# Agrobot_3_0.net
KiCad netlist of a schematic drawn in Altium Designer
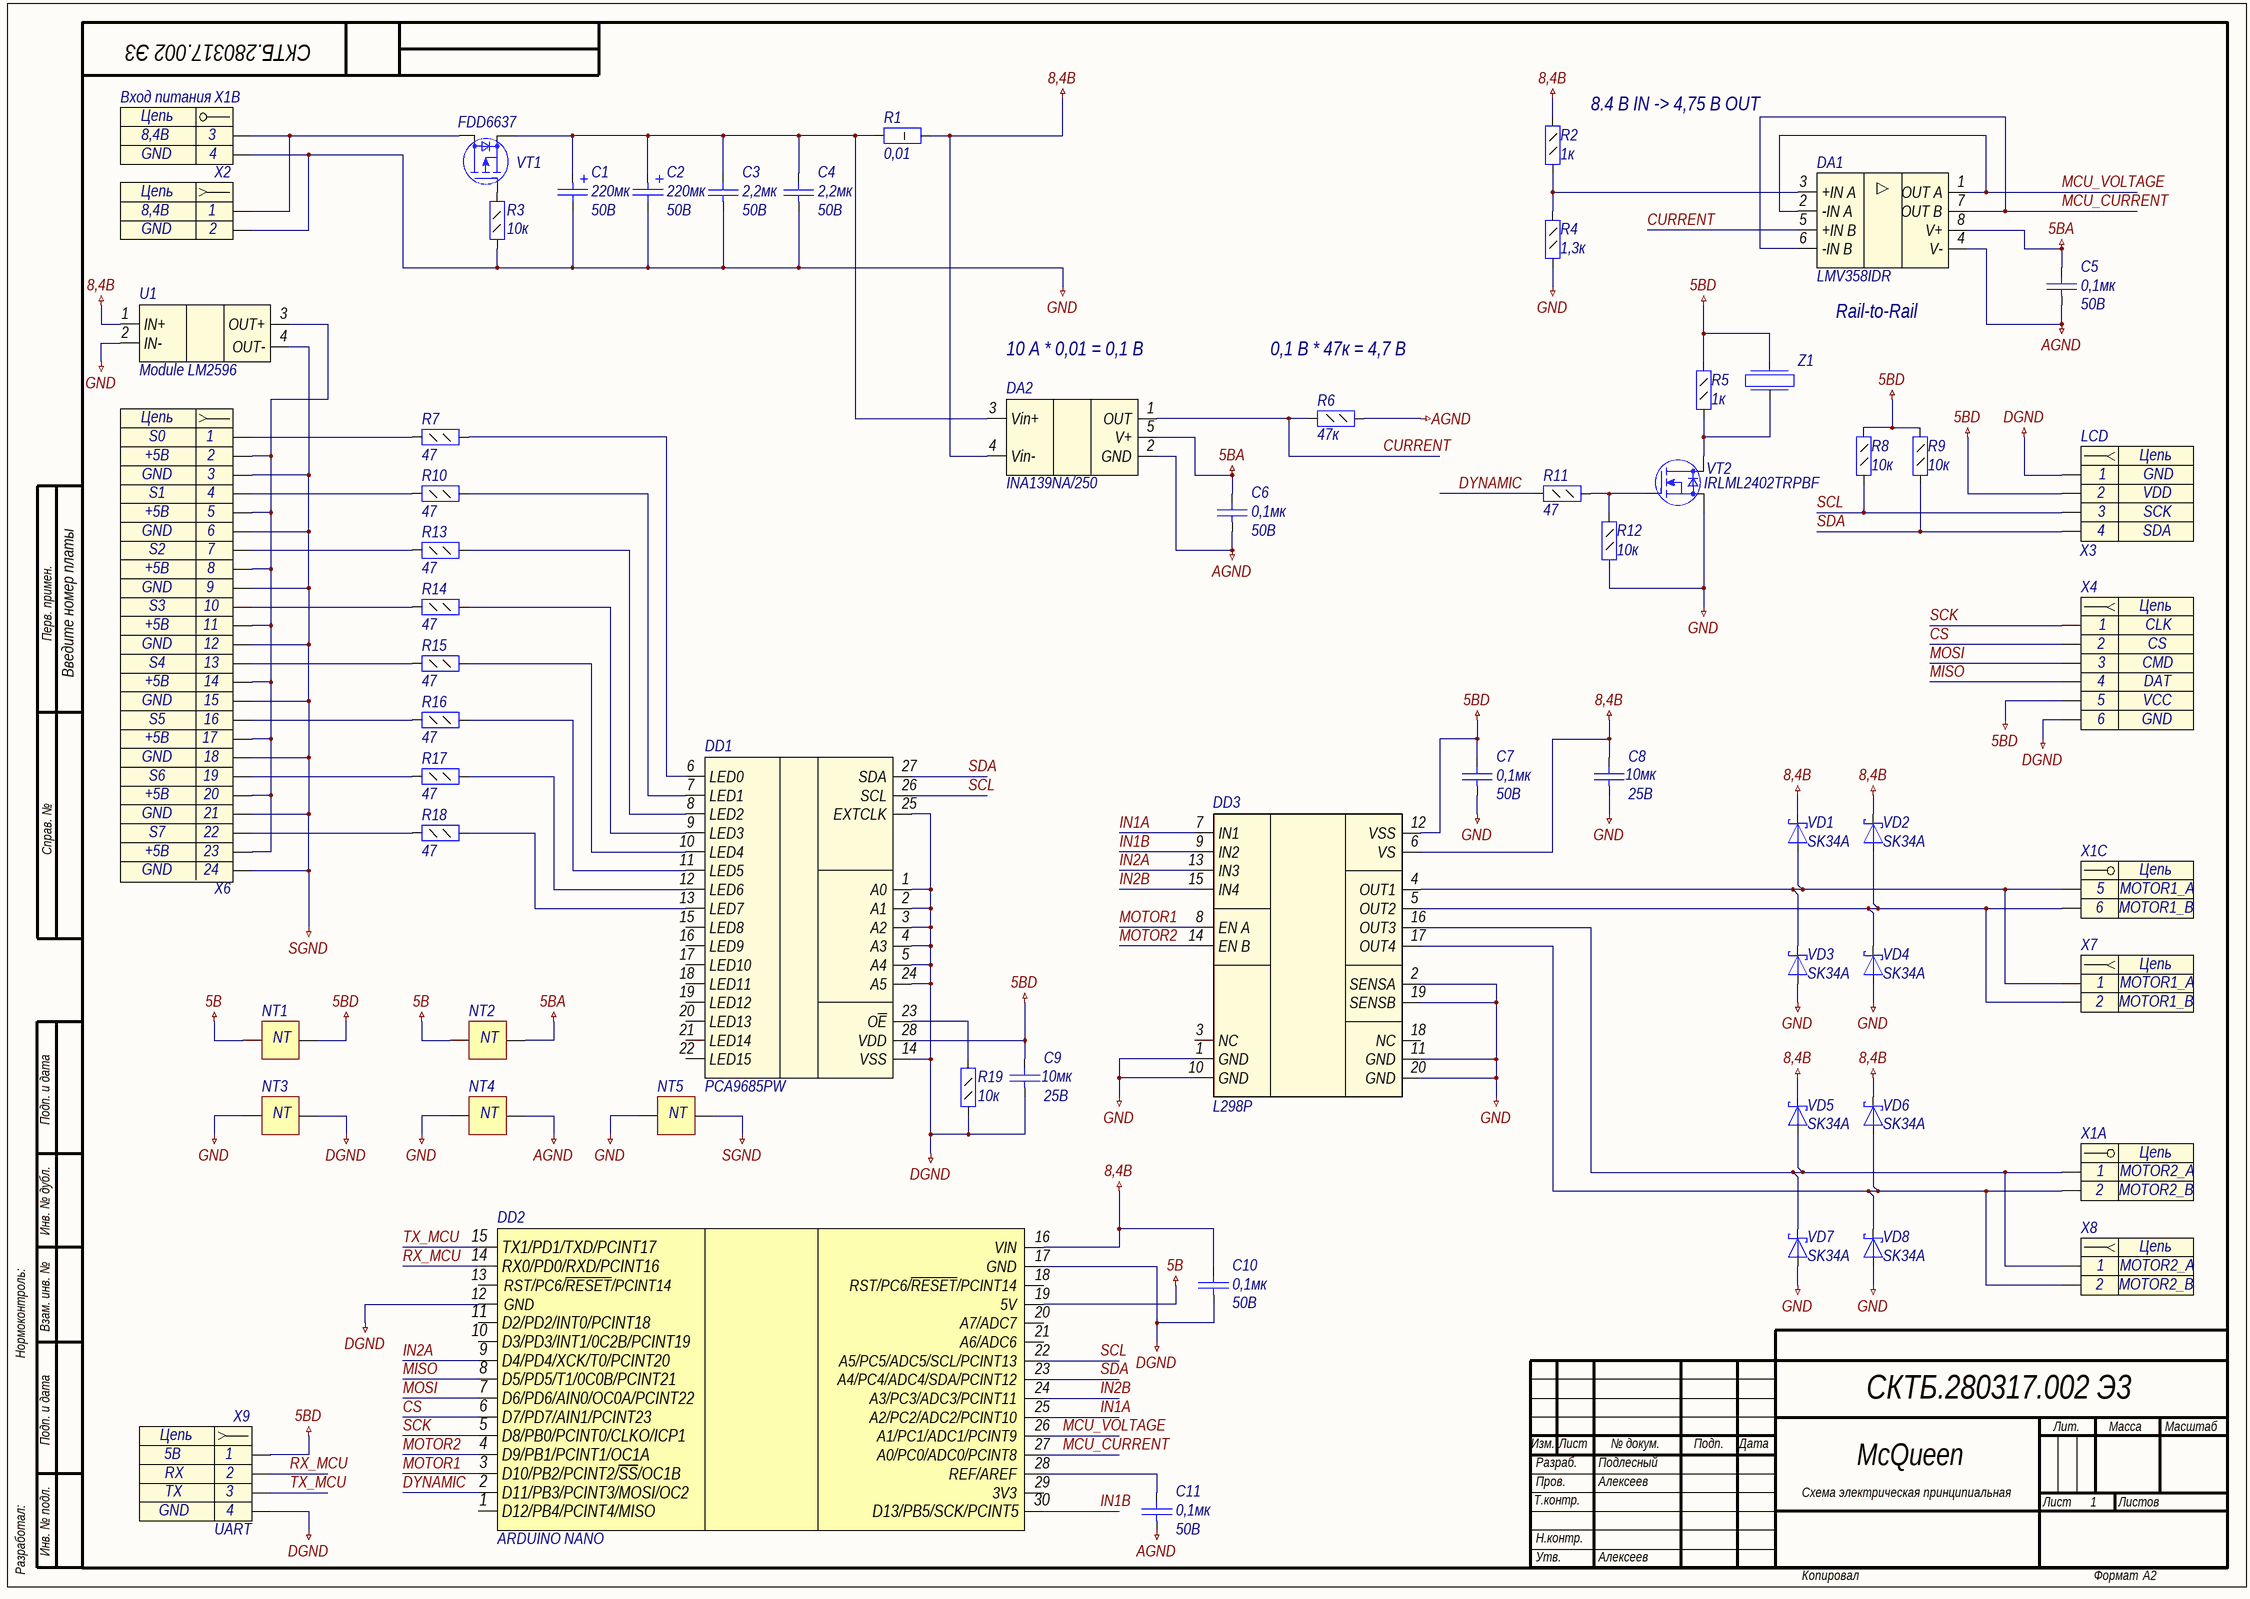
[diagram p0: Agrobot_3.0.SchDoc]

(export (version "E")
  (design (tool "Eeschema 10.0.6"))
  (components
    (comp (ref "C1")
      (value "220мк")
      (footprint "Cap_SMD_radial_polar(10x10.5)")
      (description "Конденсатор полярный")
      (fields
        (field (name "VOLTAGE") "50В")
        (field (name "PART NUMBER") "ECAP SMD")
        (field (name "Comment") "Capacitor_pol")
      )
      (libsource (lib "MOP44") (part "Capacitor_pol"))
    )
    (comp (ref "C2")
      (value "220мк")
      (footprint "Cap_SMD_radial_polar(10x10.5)")
      (description "Конденсатор полярный")
      (fields
        (field (name "VOLTAGE") "50В")
        (field (name "PART NUMBER") "ECAP SMD")
        (field (name "Comment") "Capacitor_pol")
      )
      (libsource (lib "MOP44") (part "Capacitor_pol"))
    )
    (comp (ref "C3")
      (value "2,2мк")
      (footprint "C1206")
      (description "Конденсатор")
      (fields
        (field (name "VOLTAGE") "50В")
        (field (name "PART NUMBER") "GRM31CR71H225KA88**L")
        (field (name "Comment") "Capacitor")
      )
      (libsource (lib "MOP44") (part "Capacitor"))
    )
    (comp (ref "C4")
      (value "2,2мк")
      (footprint "C1206")
      (description "Конденсатор")
      (fields
        (field (name "VOLTAGE") "50В")
        (field (name "PART NUMBER") "GRM31CR71H225KA88**L")
        (field (name "Comment") "Capacitor")
      )
      (libsource (lib "MOP44") (part "Capacitor"))
    )
    (comp (ref "C5")
      (value "0,1мк")
      (footprint "C0805")
      (description "Конденсатор")
      (fields
        (field (name "VOLTAGE") "50B")
        (field (name "PART NUMBER") "GRM21BR71E225K")
        (field (name "Comment") "Capacitor")
      )
      (libsource (lib "MOP44") (part "Capacitor"))
    )
    (comp (ref "C6")
      (value "0,1мк")
      (footprint "C0805")
      (description "Конденсатор")
      (fields
        (field (name "VOLTAGE") "50B")
        (field (name "PART NUMBER") "GRM21BR71E225K")
        (field (name "Comment") "Capacitor")
      )
      (libsource (lib "MOP44") (part "Capacitor"))
    )
    (comp (ref "C7")
      (value "0,1мк")
      (footprint "C0805")
      (description "Конденсатор")
      (fields
        (field (name "VOLTAGE") "50B")
        (field (name "PART NUMBER") "GRM21BR71E225K")
        (field (name "Comment") "Capacitor")
      )
      (libsource (lib "MOP44") (part "Capacitor"))
    )
    (comp (ref "C8")
      (value "10мк")
      (footprint "C1210")
      (description "Конденсатор")
      (fields
        (field (name "VOLTAGE") "25В")
        (field (name "PART NUMBER") "GRM32ER61A106K")
        (field (name "Comment") "Capacitor")
      )
      (libsource (lib "MOP44") (part "Capacitor"))
    )
    (comp (ref "C9")
      (value "10мк")
      (footprint "C1210")
      (description "Конденсатор")
      (fields
        (field (name "VOLTAGE") "25В")
        (field (name "PART NUMBER") "GRM32ER61A106K")
        (field (name "Comment") "Capacitor")
      )
      (libsource (lib "MOP44") (part "Capacitor"))
    )
    (comp (ref "C10")
      (value "0,1мк")
      (footprint "C0805")
      (description "Конденсатор")
      (fields
        (field (name "VOLTAGE") "50B")
        (field (name "PART NUMBER") "GRM21BR71E225K")
        (field (name "Comment") "Capacitor")
      )
      (libsource (lib "MOP44") (part "Capacitor"))
    )
    (comp (ref "C11")
      (value "0,1мк")
      (footprint "C0805")
      (description "Конденсатор")
      (fields
        (field (name "VOLTAGE") "50B")
        (field (name "PART NUMBER") "GRM21BR71E225K")
        (field (name "Comment") "Capacitor")
      )
      (libsource (lib "MOP44") (part "Capacitor"))
    )
    (comp (ref "DA1")
      (value "LMV358IDR")
      (footprint "SO8")
      (description "LOW-VOLTAGE RAIL-TO-RAIL OUTPUT OPERATIONAL AMPLIFIERS")
      (libsource (lib "MOP44") (part "LMV358IDR"))
    )
    (comp (ref "DA2")
      (value "INA139NA/250")
      (footprint "SOT23-5")
      (description "Измерительный датчик тока")
      (libsource (lib "MOP44") (part "INA139NA/250"))
    )
    (comp (ref "DD1")
      (value "PCA9685PW")
      (footprint "TSSOP28")
      (description "Драйвер светодиода, 16 выходов")
      (libsource (lib "MOP44") (part "PCA9685PW"))
    )
    (comp (ref "DD2")
      (value "ARDUINO NANO")
      (footprint "ARDUINO NANO")
      (description "Отладочная плата ATmega328")
      (libsource (lib "MOP44") (part "ARDUINO NANO"))
    )
    (comp (ref "DD3")
      (value "L298P")
      (footprint "POWERSO20")
      (description "FULL BRIDGE DC MOTOR DRIVER")
      (libsource (lib "MOP44") (part "L298P"))
    )
    (comp (ref "NT1")
      (value "Pofigistor")
      (footprint "Pofigistor0603")
      (libsource (lib "MOP44") (part "Pofigistor"))
    )
    (comp (ref "NT2")
      (value "Pofigistor")
      (footprint "Pofigistor0603")
      (libsource (lib "MOP44") (part "Pofigistor"))
    )
    (comp (ref "NT3")
      (value "Pofigistor")
      (footprint "Pofigistor0603")
      (libsource (lib "MOP44") (part "Pofigistor"))
    )
    (comp (ref "NT4")
      (value "Pofigistor")
      (footprint "Pofigistor0603")
      (libsource (lib "MOP44") (part "Pofigistor"))
    )
    (comp (ref "NT5")
      (value "Pofigistor")
      (footprint "Pofigistor0603")
      (libsource (lib "MOP44") (part "Pofigistor"))
    )
    (comp (ref "R1")
      (value "0,01")
      (footprint "R2512")
      (description "Резистор")
      (fields (field (name "POWER") "1Вт") (field (name "Comment") "Resistor_1Вт"))
      (libsource (lib "MOP44") (part "Resistor_1Вт"))
    )
    (comp (ref "R2")
      (value "1к")
      (footprint "R0805")
      (description "Резистор")
      (fields (field (name "POWER") "0,125Вт") (field (name "Comment") "Resistor_0,125Вт"))
      (libsource (lib "") (part "Resistor_0,125Вт_1"))
    )
    (comp (ref "R3")
      (value "10к")
      (footprint "R0805")
      (description "Резистор")
      (fields (field (name "PART NUMBER") "RC0805FR-0710KL") (field (name "POWER") "0,125Вт"))
      (libsource (lib "") (part "Resistor_0,125Вт_2"))
    )
    (comp (ref "R4")
      (value "1,3к")
      (footprint "R0805")
      (description "Резистор")
      (fields (field (name "POWER") "0,125Вт") (field (name "Comment") "Resistor_0,125Вт"))
      (libsource (lib "") (part "Resistor_0,125Вт_1"))
    )
    (comp (ref "R5")
      (value "1к")
      (footprint "R0805")
      (description "Резистор")
      (fields (field (name "POWER") "0,125Вт") (field (name "Comment") "Resistor_0,125Вт"))
      (libsource (lib "") (part "Resistor_0,125Вт_1"))
    )
    (comp (ref "R6")
      (value "47к")
      (footprint "R0805")
      (description "Резистор")
      (fields (field (name "POWER") "0,125Вт") (field (name "Comment") "Resistor_0,125Вт"))
      (libsource (lib "") (part "Resistor_0,125Вт_3"))
    )
    (comp (ref "R7")
      (value "47")
      (footprint "R0805")
      (description "Резистор")
      (fields (field (name "PART NUMBER") "RC0805FR-0747RL") (field (name "POWER") "0,125Вт"))
      (libsource (lib "MOP44") (part "Resistor_0,125Вт"))
    )
    (comp (ref "R8")
      (value "10к")
      (footprint "R0805")
      (description "Резистор")
      (fields (field (name "POWER") "0,125Вт") (field (name "Comment") "Resistor_0,125Вт"))
      (libsource (lib "") (part "Resistor_0,125Вт_1"))
    )
    (comp (ref "R9")
      (value "10к")
      (footprint "R0805")
      (description "Резистор")
      (fields (field (name "POWER") "0,125Вт") (field (name "Comment") "Resistor_0,125Вт"))
      (libsource (lib "") (part "Resistor_0,125Вт_1"))
    )
    (comp (ref "R10")
      (value "47")
      (footprint "R0805")
      (description "Резистор")
      (fields (field (name "PART NUMBER") "RC0805FR-0747RL") (field (name "POWER") "0,125Вт"))
      (libsource (lib "MOP44") (part "Resistor_0,125Вт"))
    )
    (comp (ref "R11")
      (value "47")
      (footprint "R0805")
      (description "Резистор")
      (fields (field (name "POWER") "0,125Вт") (field (name "Comment") "Resistor_0,125Вт"))
      (libsource (lib "") (part "Resistor_0,125Вт_3"))
    )
    (comp (ref "R12")
      (value "10к")
      (footprint "R0805")
      (description "Резистор")
      (fields (field (name "POWER") "0,125Вт") (field (name "Comment") "Resistor_0,125Вт"))
      (libsource (lib "") (part "Resistor_0,125Вт_1"))
    )
    (comp (ref "R13")
      (value "47")
      (footprint "R0805")
      (description "Резистор")
      (fields (field (name "PART NUMBER") "RC0805FR-0747RL") (field (name "POWER") "0,125Вт"))
      (libsource (lib "MOP44") (part "Resistor_0,125Вт"))
    )
    (comp (ref "R14")
      (value "47")
      (footprint "R0805")
      (description "Резистор")
      (fields (field (name "PART NUMBER") "RC0805FR-0747RL") (field (name "POWER") "0,125Вт"))
      (libsource (lib "MOP44") (part "Resistor_0,125Вт"))
    )
    (comp (ref "R15")
      (value "47")
      (footprint "R0805")
      (description "Резистор")
      (fields (field (name "PART NUMBER") "RC0805FR-0747RL") (field (name "POWER") "0,125Вт"))
      (libsource (lib "MOP44") (part "Resistor_0,125Вт"))
    )
    (comp (ref "R16")
      (value "47")
      (footprint "R0805")
      (description "Резистор")
      (fields (field (name "PART NUMBER") "RC0805FR-0747RL") (field (name "POWER") "0,125Вт"))
      (libsource (lib "MOP44") (part "Resistor_0,125Вт"))
    )
    (comp (ref "R17")
      (value "47")
      (footprint "R0805")
      (description "Резистор")
      (fields (field (name "PART NUMBER") "RC0805FR-0747RL") (field (name "POWER") "0,125Вт"))
      (libsource (lib "MOP44") (part "Resistor_0,125Вт"))
    )
    (comp (ref "R18")
      (value "47")
      (footprint "R0805")
      (description "Резистор")
      (fields (field (name "PART NUMBER") "RC0805FR-0747RL") (field (name "POWER") "0,125Вт"))
      (libsource (lib "MOP44") (part "Resistor_0,125Вт"))
    )
    (comp (ref "R19")
      (value "10к")
      (footprint "R0805")
      (description "Резистор")
      (fields (field (name "POWER") "0,125Вт") (field (name "Comment") "Resistor_0,125Вт"))
      (libsource (lib "") (part "Resistor_0,125Вт_2"))
    )
    (comp (ref "U1")
      (value "Module LM2596")
      (footprint "module LM2596")
      (description "Low-Dropout Regulator for 5-V to 3.3-V Conversion")
      (libsource (lib "MOP44") (part "Module LM2596"))
    )
    (comp (ref "VD1")
      (value "DiodeSchottky")
      (footprint "SMA")
      (description "Диод Шоттки")
      (fields (field (name "PART NUMBER") "SK34A"))
      (libsource (lib "MOP44") (part "DiodeSchottky"))
    )
    (comp (ref "VD2")
      (value "DiodeSchottky")
      (footprint "SMA")
      (description "Диод Шоттки")
      (fields (field (name "PART NUMBER") "SK34A"))
      (libsource (lib "MOP44") (part "DiodeSchottky"))
    )
    (comp (ref "VD3")
      (value "DiodeSchottky")
      (footprint "SMA")
      (description "Диод Шоттки")
      (fields (field (name "PART NUMBER") "SK34A"))
      (libsource (lib "MOP44") (part "DiodeSchottky"))
    )
    (comp (ref "VD4")
      (value "DiodeSchottky")
      (footprint "SMA")
      (description "Диод Шоттки")
      (fields (field (name "PART NUMBER") "SK34A"))
      (libsource (lib "MOP44") (part "DiodeSchottky"))
    )
    (comp (ref "VD5")
      (value "DiodeSchottky")
      (footprint "SMA")
      (description "Диод Шоттки")
      (fields (field (name "PART NUMBER") "SK34A"))
      (libsource (lib "MOP44") (part "DiodeSchottky"))
    )
    (comp (ref "VD6")
      (value "DiodeSchottky")
      (footprint "SMA")
      (description "Диод Шоттки")
      (fields (field (name "PART NUMBER") "SK34A"))
      (libsource (lib "MOP44") (part "DiodeSchottky"))
    )
    (comp (ref "VD7")
      (value "DiodeSchottky")
      (footprint "SMA")
      (description "Диод Шоттки")
      (fields (field (name "PART NUMBER") "SK34A"))
      (libsource (lib "MOP44") (part "DiodeSchottky"))
    )
    (comp (ref "VD8")
      (value "DiodeSchottky")
      (footprint "SMA")
      (description "Диод Шоттки")
      (fields (field (name "PART NUMBER") "SK34A"))
      (libsource (lib "MOP44") (part "DiodeSchottky"))
    )
    (comp (ref "VT1")
      (value "P-MOSFET")
      (footprint "DPAK")
      (description "N-MOSFET")
      (fields (field (name "PART NUMBER") "FDD6637") (field (name "MANUFACTURER") "Fairchild Semiconductor"))
      (libsource (lib "MOP44") (part "P-MOSFET"))
    )
    (comp (ref "VT2")
      (value "N-MOSFET")
      (footprint "SOT23-3")
      (fields (field (name "PART NUMBER") "IRLML2402TRPBF"))
      (libsource (lib "MOP44") (part "N-MOSFET"))
    )
    (comp (ref "X1")
      (value "Вход питания")
      (footprint "TERMINAL-6WAY-5MM")
      (description "POWER")
      (libsource (lib "MOP44") (part "Header_6_motor"))
    )
    (comp (ref "X2")
      (value "Header_2_sct")
      (footprint "2HOLE_2.5")
      (description "Разъем - 2 конт. розетка")
      (libsource (lib "") (part "Header_2_sct_1"))
    )
    (comp (ref "X3")
      (value "LCD")
      (footprint "PLS-4HOLES")
      (description "Разъем - 4 конт. розетка")
      (libsource (lib "") (part "Header_4_sct_1"))
    )
    (comp (ref "X4")
      (value "Header_6_sct")
      (footprint "PSP_ANTENNA")
      (description "Разъем - 6 конт. розетка")
      (libsource (lib "MOP44") (part "Header_6_sct"))
    )
    (comp (ref "X6")
      (value "Header_24_sct")
      (footprint "PLS-24-3")
      (description "Разъем - 5 конт. розетка")
      (libsource (lib "MOP44") (part "Header_24_sct"))
    )
    (comp (ref "X7")
      (value "Header_2_sct")
      (footprint "2HOLE_2.5")
      (description "Разъем - 2 конт. розетка")
      (libsource (lib "MOP44") (part "Header_2_sct"))
    )
    (comp (ref "X8")
      (value "Header_2_sct")
      (footprint "2HOLE_2.5")
      (description "Разъем - 2 конт. розетка")
      (libsource (lib "MOP44") (part "Header_2_sct"))
    )
    (comp (ref "X9")
      (value "UART")
      (footprint "PLS-4HOLES")
      (description "Разъем - 4 конт. розетка")
      (libsource (lib "MOP44") (part "Header_4_sct"))
    )
    (comp (ref "Z1")
      (value "~")
      (footprint "Buzzer_9mm")
      (description "Пьезоизлучатель звуковой без генератора")
      (fields (field (name "PART NUMBER") "HC0905F"))
      (libsource (lib "MOP44") (part "Buzzer"))
    )
  )
  (nets
    (net (code "1") (name "/CS") (class "Default")
      (node (ref "DD2") (pin "6") (pinfunction "D7/PD7/AIN1/PCINT23_6") (pintype "passive"))
      (node (ref "X4") (pin "2") (pinfunction "2_2") (pintype "passive"))
    )
    (net (code "2") (name "/CURRENT") (class "Default")
      (node (ref "DA1") (pin "5") (pinfunction "+IN_B_5") (pintype "passive"))
      (node (ref "DA2") (pin "1") (pinfunction "OUT_1") (pintype "power_in"))
      (node (ref "R6") (pin "2") (pinfunction "2_2") (pintype "passive"))
    )
    (net (code "3") (name "/DYNAMIC") (class "Default")
      (node (ref "DD2") (pin "2") (pinfunction "D11/PB3/PCINT3/MOSI/OC2_2") (pintype "passive"))
      (node (ref "R11") (pin "2") (pinfunction "2_2") (pintype "passive"))
    )
    (net (code "4") (name "/IN1A") (class "Default")
      (node (ref "DD2") (pin "25") (pinfunction "A2/PC2/ADC2/PCINT10_25") (pintype "passive"))
      (node (ref "DD3") (pin "7") (pinfunction "IN1_7") (pintype "passive"))
    )
    (net (code "5") (name "/IN1B") (class "Default")
      (node (ref "DD2") (pin "30") (pinfunction "D13/PB5/SCK/PCINT5_30") (pintype "passive"))
      (node (ref "DD3") (pin "9") (pinfunction "IN2_9") (pintype "passive"))
    )
    (net (code "6") (name "/IN2A") (class "Default")
      (node (ref "DD2") (pin "9") (pinfunction "D4/PD4/XCK/T0/PCINT20_9") (pintype "passive"))
      (node (ref "DD3") (pin "13") (pinfunction "IN3_13") (pintype "passive"))
    )
    (net (code "7") (name "/IN2B") (class "Default")
      (node (ref "DD2") (pin "24") (pinfunction "A3/PC3/ADC3/PCINT11_24") (pintype "passive"))
      (node (ref "DD3") (pin "15") (pinfunction "IN4_15") (pintype "passive"))
    )
    (net (code "8") (name "/MCU_CURRENT") (class "Default")
      (node (ref "DA1") (pin "6") (pinfunction "-IN_B_6") (pintype "passive"))
      (node (ref "DA1") (pin "7") (pinfunction "OUT_B_7") (pintype "passive"))
      (node (ref "DD2") (pin "27") (pinfunction "A0/PC0/ADC0/PCINT8_27") (pintype "passive"))
    )
    (net (code "9") (name "/MCU_VOLTAGE") (class "Default")
      (node (ref "DA1") (pin "1") (pinfunction "OUT_A_1") (pintype "passive"))
      (node (ref "DA1") (pin "2") (pinfunction "-IN_A_2") (pintype "passive"))
      (node (ref "DD2") (pin "26") (pinfunction "A1/PC1/ADC1/PCINT9_26") (pintype "passive"))
    )
    (net (code "10") (name "/MISO") (class "Default")
      (node (ref "DD2") (pin "8") (pinfunction "D5/PD5/T1/0C0B/PCINT21_8") (pintype "passive"))
      (node (ref "X4") (pin "4") (pinfunction "4_4") (pintype "passive"))
    )
    (net (code "11") (name "/MOSI") (class "Default")
      (node (ref "DD2") (pin "7") (pinfunction "D6/PD6/AIN0/OC0A/PCINT22_7") (pintype "passive"))
      (node (ref "X4") (pin "3") (pinfunction "3_3") (pintype "passive"))
    )
    (net (code "12") (name "/MOTOR1") (class "Default")
      (node (ref "DD2") (pin "3") (pinfunction "D10/PB2/PCINT2/~{SS}/OC1B_3") (pintype "passive"))
      (node (ref "DD3") (pin "8") (pinfunction "EN_A_8") (pintype "passive"))
    )
    (net (code "13") (name "/MOTOR2") (class "Default")
      (node (ref "DD2") (pin "4") (pinfunction "D9/PB1/PCINT1/OC1A_4") (pintype "passive"))
      (node (ref "DD3") (pin "14") (pinfunction "EN_B_14") (pintype "passive"))
    )
    (net (code "14") (name "/RX_MCU") (class "Default")
      (node (ref "DD2") (pin "14") (pinfunction "RX0/PD0/RXD/PCINT16_14") (pintype "passive"))
      (node (ref "X9") (pin "2") (pinfunction "2_2") (pintype "passive"))
    )
    (net (code "15") (name "/SCK") (class "Default")
      (node (ref "DD2") (pin "5") (pinfunction "D8/PB0/PCINT0/CLKO/ICP1_5") (pintype "passive"))
      (node (ref "X4") (pin "1") (pinfunction "1_1") (pintype "passive"))
    )
    (net (code "16") (name "/SCL") (class "Default")
      (node (ref "DD1") (pin "26") (pinfunction "SCL_26") (pintype "power_in"))
      (node (ref "DD2") (pin "22") (pinfunction "A5/PC5/ADC5/SCL/PCINT13_22") (pintype "passive"))
      (node (ref "R8") (pin "2") (pinfunction "2_2") (pintype "passive"))
      (node (ref "X3") (pin "3") (pinfunction "3_3") (pintype "passive"))
    )
    (net (code "17") (name "/SDA") (class "Default")
      (node (ref "DD1") (pin "27") (pinfunction "SDA_27") (pintype "power_in"))
      (node (ref "DD2") (pin "23") (pinfunction "A4/PC4/ADC4/SDA/PCINT12_23") (pintype "passive"))
      (node (ref "R9") (pin "2") (pinfunction "2_2") (pintype "passive"))
      (node (ref "X3") (pin "4") (pinfunction "4_4") (pintype "passive"))
    )
    (net (code "18") (name "/TX_MCU") (class "Default")
      (node (ref "DD2") (pin "15") (pinfunction "TX1/PD1/TXD/PCINT17_15") (pintype "passive"))
      (node (ref "X9") (pin "3") (pinfunction "3_3") (pintype "passive"))
    )
    (net (code "19") (name "5В") (class "Default")
      (node (ref "DD2") (pin "19") (pinfunction "5V_19") (pintype "passive"))
      (node (ref "NT1") (pin "1") (pinfunction "1_1") (pintype "passive"))
      (node (ref "NT2") (pin "1") (pinfunction "1_1") (pintype "passive"))
    )
    (net (code "20") (name "5ВA") (class "Default")
      (node (ref "C5") (pin "2") (pinfunction "2_2") (pintype "passive"))
      (node (ref "C6") (pin "2") (pinfunction "2_2") (pintype "passive"))
      (node (ref "DA1") (pin "8") (pinfunction "V+_8") (pintype "passive"))
      (node (ref "DA2") (pin "5") (pinfunction "V+_5") (pintype "power_in"))
      (node (ref "NT2") (pin "2") (pinfunction "2_2") (pintype "passive"))
    )
    (net (code "21") (name "5ВD") (class "Default")
      (node (ref "C7") (pin "2") (pinfunction "2_2") (pintype "passive"))
      (node (ref "C9") (pin "2") (pinfunction "2_2") (pintype "passive"))
      (node (ref "DD1") (pin "28") (pinfunction "VDD_28") (pintype "power_in"))
      (node (ref "DD3") (pin "12") (pinfunction "VSS_12") (pintype "passive"))
      (node (ref "NT1") (pin "2") (pinfunction "2_2") (pintype "passive"))
      (node (ref "R5") (pin "1") (pinfunction "1_1") (pintype "passive"))
      (node (ref "R8") (pin "1") (pinfunction "1_1") (pintype "passive"))
      (node (ref "R9") (pin "1") (pinfunction "1_1") (pintype "passive"))
      (node (ref "X3") (pin "2") (pinfunction "2_2") (pintype "passive"))
      (node (ref "X4") (pin "5") (pinfunction "5_5") (pintype "passive"))
      (node (ref "X9") (pin "1") (pinfunction "1_1") (pintype "passive"))
      (node (ref "Z1") (pin "2") (pinfunction "2_2") (pintype "passive"))
    )
    (net (code "22") (name "8,4В") (class "Default")
      (node (ref "C10") (pin "2") (pinfunction "2_2") (pintype "passive"))
      (node (ref "C8") (pin "2") (pinfunction "2_2") (pintype "passive"))
      (node (ref "DA2") (pin "4") (pinfunction "Vin-_4") (pintype "power_in"))
      (node (ref "DD2") (pin "16") (pinfunction "VIN_16") (pintype "passive"))
      (node (ref "DD3") (pin "6") (pinfunction "VS_6") (pintype "passive"))
      (node (ref "R1") (pin "2") (pinfunction "5_2") (pintype "passive"))
      (node (ref "R2") (pin "1") (pinfunction "1_1") (pintype "passive"))
      (node (ref "U1") (pin "1") (pinfunction "IN+_1") (pintype "power_in"))
      (node (ref "VD1") (pin "1") (pinfunction "K_1") (pintype "passive"))
      (node (ref "VD2") (pin "1") (pinfunction "K_1") (pintype "passive"))
      (node (ref "VD5") (pin "1") (pinfunction "K_1") (pintype "passive"))
      (node (ref "VD6") (pin "1") (pinfunction "K_1") (pintype "passive"))
    )
    (net (code "23") (name "AGND") (class "Default")
      (node (ref "C11") (pin "1") (pinfunction "1_1") (pintype "passive"))
      (node (ref "C5") (pin "1") (pinfunction "1_1") (pintype "passive"))
      (node (ref "C6") (pin "1") (pinfunction "1_1") (pintype "passive"))
      (node (ref "DA1") (pin "4") (pinfunction "V-_4") (pintype "passive"))
      (node (ref "DA2") (pin "2") (pinfunction "GND_2") (pintype "power_in"))
      (node (ref "NT4") (pin "2") (pinfunction "2_2") (pintype "passive"))
      (node (ref "R6") (pin "1") (pinfunction "1_1") (pintype "passive"))
    )
    (net (code "24") (name "DGND") (class "Default")
      (node (ref "C10") (pin "1") (pinfunction "1_1") (pintype "passive"))
      (node (ref "C9") (pin "1") (pinfunction "1_1") (pintype "passive"))
      (node (ref "DD1") (pin "1") (pinfunction "A0_1") (pintype "power_in"))
      (node (ref "DD1") (pin "14") (pinfunction "VSS_14") (pintype "power_in"))
      (node (ref "DD1") (pin "2") (pinfunction "A1_2") (pintype "power_in"))
      (node (ref "DD1") (pin "24") (pinfunction "A5_24") (pintype "power_in"))
      (node (ref "DD1") (pin "25") (pinfunction "EXTCLK_25") (pintype "power_in"))
      (node (ref "DD1") (pin "3") (pinfunction "A2_3") (pintype "power_in"))
      (node (ref "DD1") (pin "4") (pinfunction "A3_4") (pintype "power_in"))
      (node (ref "DD1") (pin "5") (pinfunction "A4_5") (pintype "power_in"))
      (node (ref "DD2") (pin "12") (pinfunction "GND_12") (pintype "passive"))
      (node (ref "DD2") (pin "17") (pinfunction "GND_17") (pintype "passive"))
      (node (ref "NT3") (pin "2") (pinfunction "2_2") (pintype "passive"))
      (node (ref "R19") (pin "1") (pinfunction "1_1") (pintype "passive"))
      (node (ref "X3") (pin "1") (pinfunction "1_1") (pintype "passive"))
      (node (ref "X4") (pin "6") (pinfunction "6_6") (pintype "passive"))
      (node (ref "X9") (pin "4") (pinfunction "4_4") (pintype "passive"))
    )
    (net (code "25") (name "GND") (class "Default")
      (node (ref "C1") (pin "2") (pinfunction "2_2") (pintype "passive"))
      (node (ref "C2") (pin "2") (pinfunction "2_2") (pintype "passive"))
      (node (ref "C3") (pin "1") (pinfunction "1_1") (pintype "passive"))
      (node (ref "C4") (pin "1") (pinfunction "1_1") (pintype "passive"))
      (node (ref "C7") (pin "1") (pinfunction "1_1") (pintype "passive"))
      (node (ref "C8") (pin "1") (pinfunction "1_1") (pintype "passive"))
      (node (ref "DD3") (pin "1") (pinfunction "GND_1") (pintype "passive"))
      (node (ref "DD3") (pin "10") (pinfunction "GND_10") (pintype "passive"))
      (node (ref "DD3") (pin "11") (pinfunction "GND_11") (pintype "passive"))
      (node (ref "DD3") (pin "19") (pinfunction "SENSB_19") (pintype "passive"))
      (node (ref "DD3") (pin "2") (pinfunction "SENSA_2") (pintype "passive"))
      (node (ref "DD3") (pin "20") (pinfunction "GND_20") (pintype "passive"))
      (node (ref "NT3") (pin "1") (pinfunction "1_1") (pintype "passive"))
      (node (ref "NT4") (pin "1") (pinfunction "1_1") (pintype "passive"))
      (node (ref "NT5") (pin "1") (pinfunction "1_1") (pintype "passive"))
      (node (ref "R12") (pin "2") (pinfunction "2_2") (pintype "passive"))
      (node (ref "R3") (pin "1") (pinfunction "1_1") (pintype "passive"))
      (node (ref "R4") (pin "2") (pinfunction "2_2") (pintype "passive"))
      (node (ref "U1") (pin "2") (pinfunction "IN-_2") (pintype "power_in"))
      (node (ref "VD3") (pin "2") (pinfunction "A_2") (pintype "passive"))
      (node (ref "VD4") (pin "2") (pinfunction "A_2") (pintype "passive"))
      (node (ref "VD7") (pin "2") (pinfunction "A_2") (pintype "passive"))
      (node (ref "VD8") (pin "2") (pinfunction "A_2") (pintype "passive"))
      (node (ref "VT2") (pin "2") (pinfunction "S_2") (pintype "passive"))
      (node (ref "X1") (pin "4") (pinfunction "4_4") (pintype "passive"))
      (node (ref "X2") (pin "2") (pinfunction "2_2") (pintype "passive"))
    )
    (net (code "26") (name "Net-(DA1-+IN_A)") (class "Default")
      (node (ref "DA1") (pin "3") (pinfunction "+IN_A_3") (pintype "passive"))
      (node (ref "R2") (pin "2") (pinfunction "2_2") (pintype "passive"))
      (node (ref "R4") (pin "1") (pinfunction "1_1") (pintype "passive"))
    )
    (net (code "27") (name "Net-(DA2-Vin+)") (class "Default")
      (node (ref "C1") (pin "1") (pinfunction "1_1") (pintype "passive"))
      (node (ref "C2") (pin "1") (pinfunction "1_1") (pintype "passive"))
      (node (ref "C3") (pin "2") (pinfunction "2_2") (pintype "passive"))
      (node (ref "C4") (pin "2") (pinfunction "2_2") (pintype "passive"))
      (node (ref "DA2") (pin "3") (pinfunction "Vin+_3") (pintype "power_in"))
      (node (ref "R1") (pin "1") (pinfunction "1_1") (pintype "passive"))
      (node (ref "VT1") (pin "3") (pinfunction "S_3") (pintype "passive"))
    )
    (net (code "28") (name "Net-(DD1-LED0)") (class "Default")
      (node (ref "DD1") (pin "6") (pinfunction "LED0_6") (pintype "power_in"))
      (node (ref "R7") (pin "2") (pinfunction "2_2") (pintype "passive"))
    )
    (net (code "29") (name "Net-(DD1-LED1)") (class "Default")
      (node (ref "DD1") (pin "7") (pinfunction "LED1_7") (pintype "power_in"))
      (node (ref "R10") (pin "2") (pinfunction "2_2") (pintype "passive"))
    )
    (net (code "30") (name "Net-(DD1-LED2)") (class "Default")
      (node (ref "DD1") (pin "8") (pinfunction "LED2_8") (pintype "power_in"))
      (node (ref "R13") (pin "2") (pinfunction "2_2") (pintype "passive"))
    )
    (net (code "31") (name "Net-(DD1-LED3)") (class "Default")
      (node (ref "DD1") (pin "9") (pinfunction "LED3_9") (pintype "power_in"))
      (node (ref "R14") (pin "2") (pinfunction "2_2") (pintype "passive"))
    )
    (net (code "32") (name "Net-(DD1-LED4)") (class "Default")
      (node (ref "DD1") (pin "10") (pinfunction "LED4_10") (pintype "power_in"))
      (node (ref "R15") (pin "2") (pinfunction "2_2") (pintype "passive"))
    )
    (net (code "33") (name "Net-(DD1-LED5)") (class "Default")
      (node (ref "DD1") (pin "11") (pinfunction "LED5_11") (pintype "power_in"))
      (node (ref "R16") (pin "2") (pinfunction "2_2") (pintype "passive"))
    )
    (net (code "34") (name "Net-(DD1-LED6)") (class "Default")
      (node (ref "DD1") (pin "12") (pinfunction "LED6_12") (pintype "power_in"))
      (node (ref "R17") (pin "2") (pinfunction "2_2") (pintype "passive"))
    )
    (net (code "35") (name "Net-(DD1-LED7)") (class "Default")
      (node (ref "DD1") (pin "13") (pinfunction "LED7_13") (pintype "power_in"))
      (node (ref "R18") (pin "2") (pinfunction "2_2") (pintype "passive"))
    )
    (net (code "36") (name "Net-(DD1-O~{E})") (class "Default")
      (node (ref "DD1") (pin "23") (pinfunction "O~{E}_23") (pintype "power_in"))
      (node (ref "R19") (pin "2") (pinfunction "2_2") (pintype "passive"))
    )
    (net (code "37") (name "Net-(DD2-REF{slash}AREF)") (class "Default")
      (node (ref "C11") (pin "2") (pinfunction "2_2") (pintype "passive"))
      (node (ref "DD2") (pin "28") (pinfunction "REF/AREF_28") (pintype "passive"))
    )
    (net (code "38") (name "Net-(DD3-OUT1)") (class "Default")
      (node (ref "DD3") (pin "4") (pinfunction "OUT1_4") (pintype "passive"))
      (node (ref "VD1") (pin "2") (pinfunction "A_2") (pintype "passive"))
      (node (ref "VD3") (pin "1") (pinfunction "K_1") (pintype "passive"))
      (node (ref "X1") (pin "5") (pinfunction "5_5") (pintype "passive"))
      (node (ref "X7") (pin "1") (pinfunction "1_1") (pintype "passive"))
    )
    (net (code "39") (name "Net-(DD3-OUT2)") (class "Default")
      (node (ref "DD3") (pin "5") (pinfunction "OUT2_5") (pintype "passive"))
      (node (ref "VD2") (pin "2") (pinfunction "A_2") (pintype "passive"))
      (node (ref "VD4") (pin "1") (pinfunction "K_1") (pintype "passive"))
      (node (ref "X1") (pin "6") (pinfunction "6_6") (pintype "passive"))
      (node (ref "X7") (pin "2") (pinfunction "2_2") (pintype "passive"))
    )
    (net (code "40") (name "Net-(DD3-OUT3)") (class "Default")
      (node (ref "DD3") (pin "16") (pinfunction "OUT3_16") (pintype "passive"))
      (node (ref "VD5") (pin "2") (pinfunction "A_2") (pintype "passive"))
      (node (ref "VD7") (pin "1") (pinfunction "K_1") (pintype "passive"))
      (node (ref "X1") (pin "1") (pinfunction "1_1") (pintype "passive"))
      (node (ref "X8") (pin "1") (pinfunction "1_1") (pintype "passive"))
    )
    (net (code "41") (name "Net-(DD3-OUT4)") (class "Default")
      (node (ref "DD3") (pin "17") (pinfunction "OUT4_17") (pintype "passive"))
      (node (ref "VD6") (pin "2") (pinfunction "A_2") (pintype "passive"))
      (node (ref "VD8") (pin "1") (pinfunction "K_1") (pintype "passive"))
      (node (ref "X1") (pin "2") (pinfunction "2_2") (pintype "passive"))
      (node (ref "X8") (pin "2") (pinfunction "2_2") (pintype "passive"))
    )
    (net (code "42") (name "Net-(R7-Pad1)") (class "Default")
      (node (ref "R7") (pin "1") (pinfunction "1_1") (pintype "passive"))
      (node (ref "X6") (pin "1") (pinfunction "1_1") (pintype "passive"))
    )
    (net (code "43") (name "Net-(R10-Pad1)") (class "Default")
      (node (ref "R10") (pin "1") (pinfunction "1_1") (pintype "passive"))
      (node (ref "X6") (pin "4") (pinfunction "4_4") (pintype "passive"))
    )
    (net (code "44") (name "Net-(R13-Pad1)") (class "Default")
      (node (ref "R13") (pin "1") (pinfunction "1_1") (pintype "passive"))
      (node (ref "X6") (pin "7") (pinfunction "7_7") (pintype "passive"))
    )
    (net (code "45") (name "Net-(R14-Pad1)") (class "Default")
      (node (ref "R14") (pin "1") (pinfunction "1_1") (pintype "passive"))
      (node (ref "X6") (pin "10") (pinfunction "10_10") (pintype "passive"))
    )
    (net (code "46") (name "Net-(R15-Pad1)") (class "Default")
      (node (ref "R15") (pin "1") (pinfunction "1_1") (pintype "passive"))
      (node (ref "X6") (pin "13") (pinfunction "13_13") (pintype "passive"))
    )
    (net (code "47") (name "Net-(R16-Pad1)") (class "Default")
      (node (ref "R16") (pin "1") (pinfunction "1_1") (pintype "passive"))
      (node (ref "X6") (pin "16") (pinfunction "16_16") (pintype "passive"))
    )
    (net (code "48") (name "Net-(R17-Pad1)") (class "Default")
      (node (ref "R17") (pin "1") (pinfunction "1_1") (pintype "passive"))
      (node (ref "X6") (pin "19") (pinfunction "19_19") (pintype "passive"))
    )
    (net (code "49") (name "Net-(R18-Pad1)") (class "Default")
      (node (ref "R18") (pin "1") (pinfunction "1_1") (pintype "passive"))
      (node (ref "X6") (pin "22") (pinfunction "22_22") (pintype "passive"))
    )
    (net (code "50") (name "Net-(U1-OUT+)") (class "Default")
      (node (ref "U1") (pin "3") (pinfunction "OUT+_3") (pintype "power_in"))
      (node (ref "X6") (pin "11") (pinfunction "11_11") (pintype "passive"))
      (node (ref "X6") (pin "14") (pinfunction "14_14") (pintype "passive"))
      (node (ref "X6") (pin "17") (pinfunction "17_17") (pintype "passive"))
      (node (ref "X6") (pin "2") (pinfunction "2_2") (pintype "passive"))
      (node (ref "X6") (pin "20") (pinfunction "20_20") (pintype "passive"))
      (node (ref "X6") (pin "23") (pinfunction "23_23") (pintype "passive"))
      (node (ref "X6") (pin "5") (pinfunction "5_5") (pintype "passive"))
      (node (ref "X6") (pin "8") (pinfunction "8_8") (pintype "passive"))
    )
    (net (code "51") (name "Net-(VT1-D)") (class "Default")
      (node (ref "VT1") (pin "2") (pinfunction "D_2") (pintype "passive"))
      (node (ref "X1") (pin "3") (pinfunction "3_3") (pintype "passive"))
      (node (ref "X2") (pin "1") (pinfunction "1_1") (pintype "passive"))
    )
    (net (code "52") (name "Net-(VT1-G)") (class "Default")
      (node (ref "R3") (pin "2") (pinfunction "2_2") (pintype "passive"))
      (node (ref "VT1") (pin "1") (pinfunction "G_1") (pintype "passive"))
    )
    (net (code "53") (name "Net-(VT2-D)") (class "Default")
      (node (ref "R5") (pin "2") (pinfunction "2_2") (pintype "passive"))
      (node (ref "VT2") (pin "3") (pinfunction "D_3") (pintype "passive"))
      (node (ref "Z1") (pin "1") (pinfunction "1_1") (pintype "passive"))
    )
    (net (code "54") (name "Net-(VT2-G)") (class "Default")
      (node (ref "R11") (pin "1") (pinfunction "1_1") (pintype "passive"))
      (node (ref "R12") (pin "1") (pinfunction "1_1") (pintype "passive"))
      (node (ref "VT2") (pin "1") (pinfunction "G_1") (pintype "passive"))
    )
    (net (code "55") (name "SGND") (class "Default")
      (node (ref "NT5") (pin "2") (pinfunction "2_2") (pintype "passive"))
      (node (ref "U1") (pin "4") (pinfunction "OUT-_4") (pintype "power_in"))
      (node (ref "X6") (pin "12") (pinfunction "12_12") (pintype "passive"))
      (node (ref "X6") (pin "15") (pinfunction "15_15") (pintype "passive"))
      (node (ref "X6") (pin "18") (pinfunction "18_18") (pintype "passive"))
      (node (ref "X6") (pin "21") (pinfunction "21_21") (pintype "passive"))
      (node (ref "X6") (pin "24") (pinfunction "24_24") (pintype "passive"))
      (node (ref "X6") (pin "3") (pinfunction "3_3") (pintype "passive"))
      (node (ref "X6") (pin "6") (pinfunction "6_6") (pintype "passive"))
      (node (ref "X6") (pin "9") (pinfunction "9_9") (pintype "passive"))
    )
    (net (code "56") (name "unconnected-(DD1-LED8-Pad15)") (class "Default")
      (node (ref "DD1") (pin "15") (pinfunction "LED8_15") (pintype "power_in"))
    )
    (net (code "57") (name "unconnected-(DD1-LED9-Pad16)") (class "Default")
      (node (ref "DD1") (pin "16") (pinfunction "LED9_16") (pintype "power_in"))
    )
    (net (code "58") (name "unconnected-(DD1-LED10-Pad17)") (class "Default")
      (node (ref "DD1") (pin "17") (pinfunction "LED10_17") (pintype "power_in"))
    )
    (net (code "59") (name "unconnected-(DD1-LED11-Pad18)") (class "Default")
      (node (ref "DD1") (pin "18") (pinfunction "LED11_18") (pintype "power_in"))
    )
    (net (code "60") (name "unconnected-(DD1-LED12-Pad19)") (class "Default")
      (node (ref "DD1") (pin "19") (pinfunction "LED12_19") (pintype "power_in"))
    )
    (net (code "61") (name "unconnected-(DD1-LED13-Pad20)") (class "Default")
      (node (ref "DD1") (pin "20") (pinfunction "LED13_20") (pintype "power_in"))
    )
    (net (code "62") (name "unconnected-(DD1-LED14-Pad21)") (class "Default")
      (node (ref "DD1") (pin "21") (pinfunction "LED14_21") (pintype "power_in"))
    )
    (net (code "63") (name "unconnected-(DD1-LED15-Pad22)") (class "Default")
      (node (ref "DD1") (pin "22") (pinfunction "LED15_22") (pintype "power_in"))
    )
    (net (code "64") (name "unconnected-(DD2-3V3-Pad29)") (class "Default")
      (node (ref "DD2") (pin "29") (pinfunction "3V3_29") (pintype "passive"))
    )
    (net (code "65") (name "unconnected-(DD2-A6{slash}ADC6-Pad21)") (class "Default")
      (node (ref "DD2") (pin "21") (pinfunction "A6/ADC6_21") (pintype "passive"))
    )
    (net (code "66") (name "unconnected-(DD2-A7{slash}ADC7-Pad20)") (class "Default")
      (node (ref "DD2") (pin "20") (pinfunction "A7/ADC7_20") (pintype "passive"))
    )
    (net (code "67") (name "unconnected-(DD2-D2{slash}PD2{slash}INT0{slash}PCINT18-Pad11)") (class "Default")
      (node (ref "DD2") (pin "11") (pinfunction "D2/PD2/INT0/PCINT18_11") (pintype "passive"))
    )
    (net (code "68") (name "unconnected-(DD2-D3{slash}PD3{slash}INT1{slash}0C2B{slash}PCINT19-Pad10)") (class "Default")
      (node (ref "DD2") (pin "10") (pinfunction "D3/PD3/INT1/0C2B/PCINT19_10") (pintype "passive"))
    )
    (net (code "69") (name "unconnected-(DD2-D12{slash}PB4{slash}PCINT4{slash}MISO-Pad1)") (class "Default")
      (node (ref "DD2") (pin "1") (pinfunction "D12/PB4/PCINT4/MISO_1") (pintype "passive"))
    )
    (net (code "70") (name "unconnected-(DD2-RST{slash}PC6{slash}~{RESET}{slash}PCINT14-Pad13)") (class "Default")
      (node (ref "DD2") (pin "13") (pinfunction "RST/PC6/~{RESET}/PCINT14_13") (pintype "passive"))
    )
    (net (code "71") (name "unconnected-(DD2-RST{slash}PC6{slash}~{RESET}{slash}PCINT14-Pad18)") (class "Default")
      (node (ref "DD2") (pin "18") (pinfunction "RST/PC6/~{RESET}/PCINT14_18") (pintype "passive"))
    )
    (net (code "72") (name "unconnected-(DD3-NC-Pad3)") (class "Default")
      (node (ref "DD3") (pin "3") (pinfunction "NC_3") (pintype "passive"))
    )
    (net (code "73") (name "unconnected-(DD3-NC-Pad18)") (class "Default")
      (node (ref "DD3") (pin "18") (pinfunction "NC_18") (pintype "passive"))
    )
  )
)
